# SUSTAINA-Audio-Board.net
KiCad netlist of a schematic drawn in EAGLE
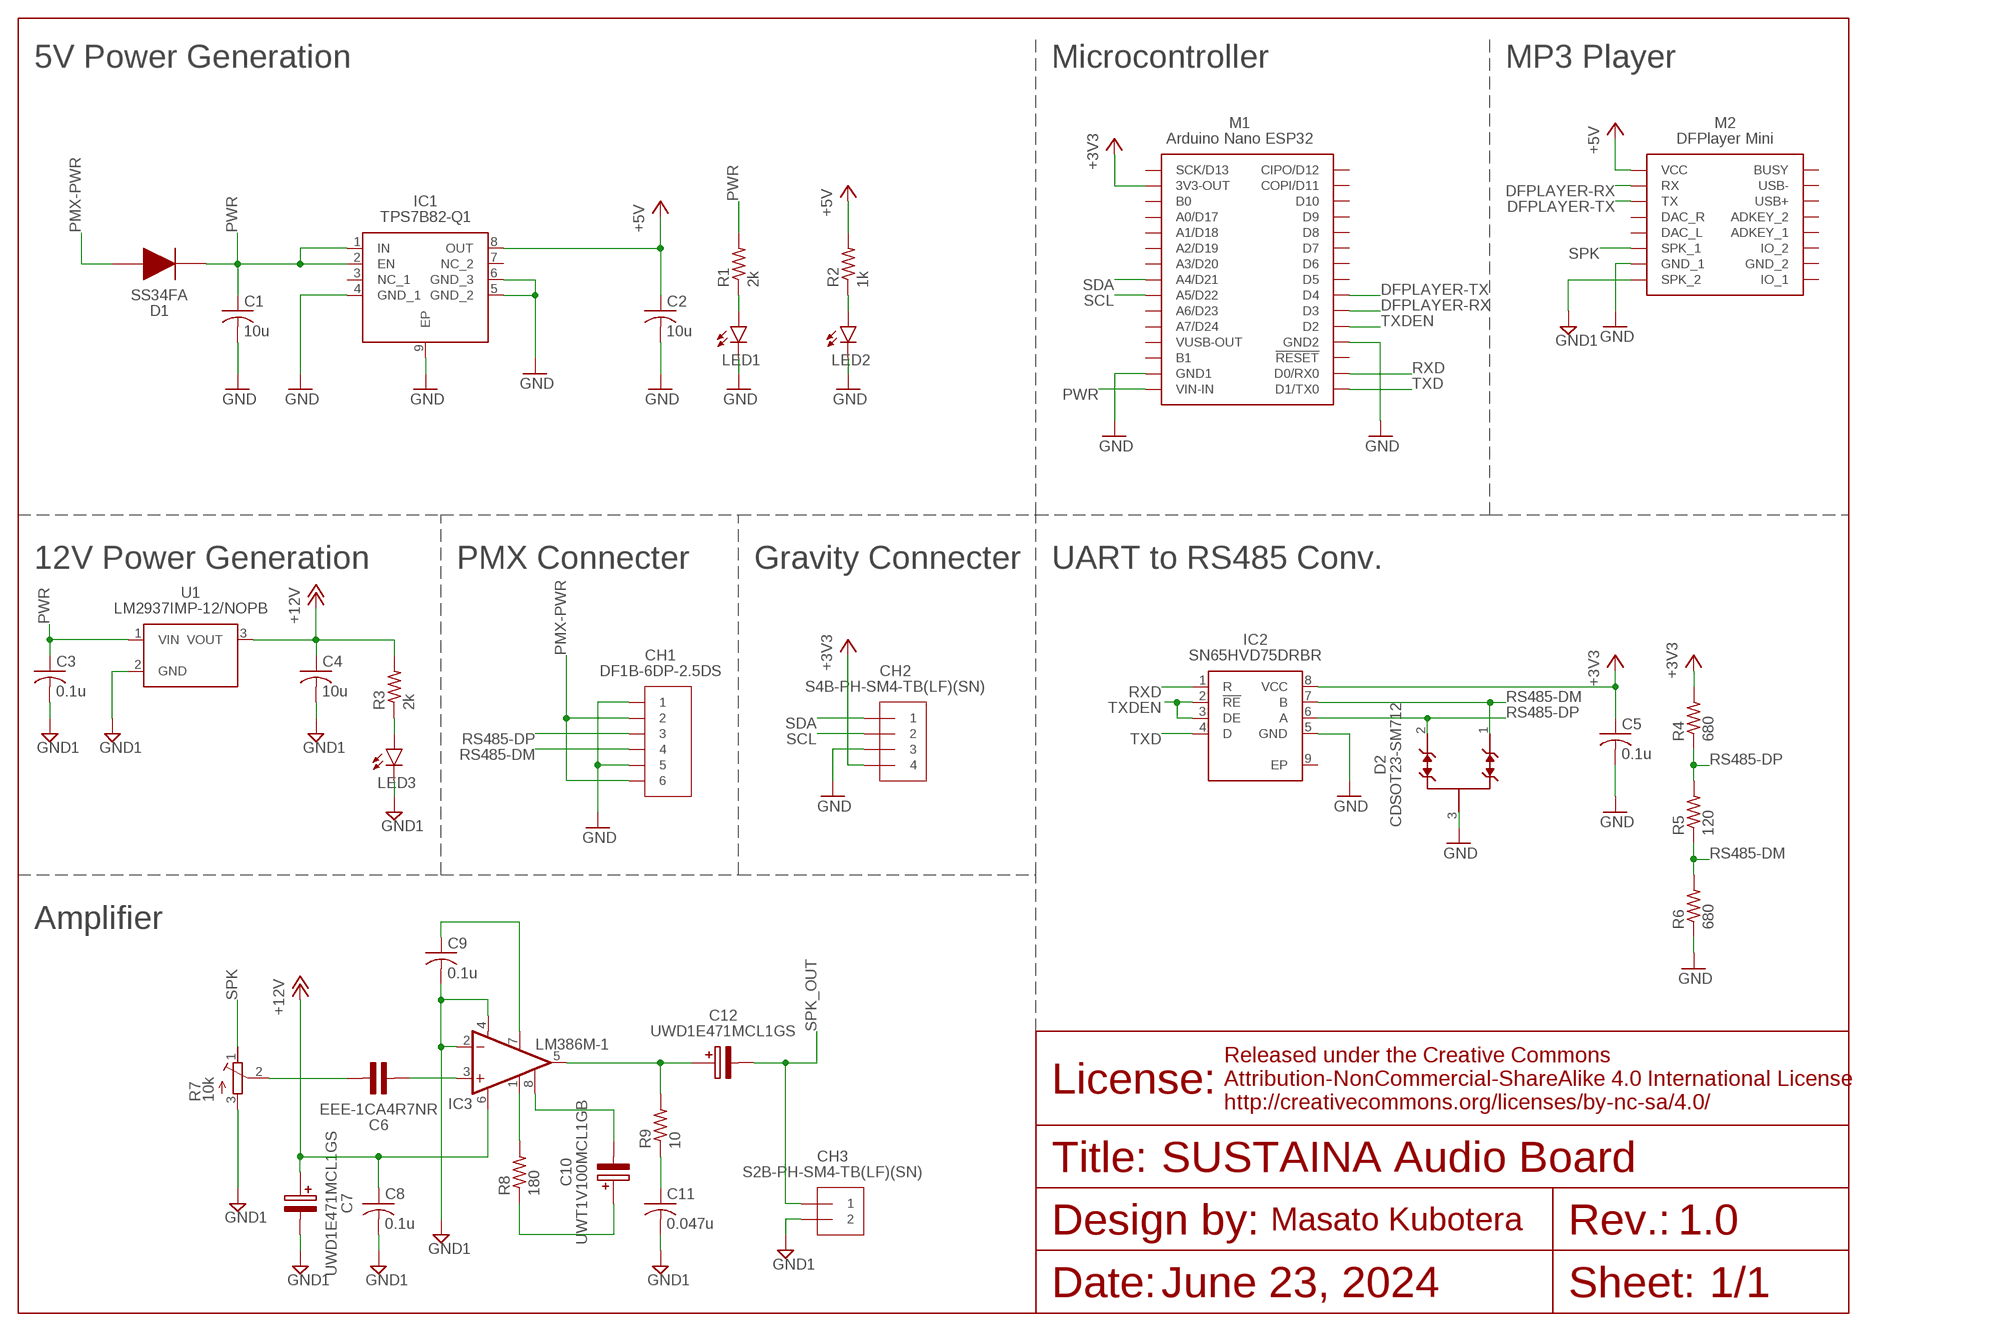
[diagram p0: schematic, sheet 1]

(export (version "E")
  (design (tool "Eeschema 10.0.6"))
  (components
    (comp (ref "C1")
      (value "10u")
      (footprint "eagle-import:C0603")
      (libsource (lib "eagle-import") (part "C-USC0603"))
    )
    (comp (ref "C2")
      (value "10u")
      (footprint "eagle-import:C0603")
      (libsource (lib "eagle-import") (part "C-USC0603"))
    )
    (comp (ref "C3")
      (value "0.1u")
      (footprint "eagle-import:C0603")
      (libsource (lib "eagle-import") (part "C-USC0603"))
    )
    (comp (ref "C4")
      (value "10u")
      (footprint "eagle-import:C0603")
      (libsource (lib "eagle-import") (part "C-USC0603"))
    )
    (comp (ref "C5")
      (value "0.1u")
      (footprint "eagle-import:C0603")
      (libsource (lib "eagle-import") (part "C-USC0603"))
    )
    (comp (ref "C6")
      (value "EEE-1CA4R7NR")
      (footprint "eagle-import:EEE-1CA4R7NR")
      (libsource (lib "eagle-import") (part "EEE-1CA4R7NR"))
    )
    (comp (ref "C7")
      (value "UWD1E471MCL1GS")
      (footprint "eagle-import:UWD1E471MCL1GS")
      (libsource (lib "eagle-import") (part "UWD1E471MCL1GS"))
    )
    (comp (ref "C8")
      (value "0.1u")
      (footprint "eagle-import:C0603")
      (libsource (lib "eagle-import") (part "C-USC0603"))
    )
    (comp (ref "C9")
      (value "0.1u")
      (footprint "eagle-import:C0603")
      (libsource (lib "eagle-import") (part "C-USC0603"))
    )
    (comp (ref "C10")
      (value "UWT1V100MCL1GB")
      (footprint "eagle-import:UWT1V100MCL1GB")
      (libsource (lib "eagle-import") (part "UWT1V100MCL1GB"))
    )
    (comp (ref "C11")
      (value "0.047u")
      (footprint "eagle-import:C050-055X075")
      (libsource (lib "eagle-import") (part "C-US050-055X075"))
    )
    (comp (ref "C12")
      (value "UWD1E471MCL1GS")
      (footprint "eagle-import:UWD1E471MCL1GS")
      (libsource (lib "eagle-import") (part "UWD1E471MCL1GS"))
    )
    (comp (ref "CH1")
      (value "DF1B-6DP-2.5DS")
      (footprint "eagle-import:DF1B-6DP-2.5DS")
      (libsource (lib "eagle-import") (part "DF1B-6DP-2.5DS"))
    )
    (comp (ref "CH2")
      (value "S4B-PH-SM4-TB(LF)(SN)")
      (footprint "eagle-import:S4B-PH-SM4-TB(LF)(SN)")
      (libsource (lib "eagle-import") (part "S4B-PH-SM4-TB(LF)(SN)"))
    )
    (comp (ref "CH3")
      (value "S2B-PH-SM4-TB(LF)(SN)")
      (footprint "eagle-import:S2B-PH-SM4-TB(LF)(SN)")
      (libsource (lib "eagle-import") (part "S2B-PH-SM4-TB(LF)(SN)"))
    )
    (comp (ref "D1")
      (value "SS34FA")
      (footprint "eagle-import:SS34FA")
      (libsource (lib "eagle-import") (part "SS34FA"))
    )
    (comp (ref "D2")
      (value "CDSOT23-SM712")
      (footprint "eagle-import:SOT-23-3")
      (libsource (lib "eagle-import") (part "CDSOT23-SM712"))
    )
    (comp (ref "IC1")
      (value "TPS7B82-Q1")
      (footprint "eagle-import:SOP65P490X110-9N")
      (libsource (lib "eagle-import") (part "TPS7B82-Q1"))
    )
    (comp (ref "IC2")
      (value "SN65HVD75DRBR")
      (footprint "eagle-import:SON65P300X300X100-9N")
      (libsource (lib "eagle-import") (part "SN65HVD75DRBR"))
    )
    (comp (ref "IC3")
      (value "LM386M-1")
      (footprint "eagle-import:SO08")
      (libsource (lib "eagle-import") (part "LM386?-M1"))
    )
    (comp (ref "LED1")
      (value "LEDSML0603")
      (footprint "eagle-import:SML0603")
      (libsource (lib "eagle-import") (part "LEDSML0603"))
    )
    (comp (ref "LED2")
      (value "LEDSML0603")
      (footprint "eagle-import:SML0603")
      (libsource (lib "eagle-import") (part "LEDSML0603"))
    )
    (comp (ref "LED3")
      (value "LEDSML0603")
      (footprint "eagle-import:SML0603")
      (libsource (lib "eagle-import") (part "LEDSML0603"))
    )
    (comp (ref "M1")
      (value "NANO-ESP32")
      (footprint "eagle-import:NANO-ESP32")
      (libsource (lib "eagle-import") (part "NANO-ESP32"))
    )
    (comp (ref "M2")
      (value "DFPLAYER_MINI")
      (footprint "eagle-import:DFPLAYER_MINI")
      (libsource (lib "eagle-import") (part "DFPLAYER_MINI"))
    )
    (comp (ref "R1")
      (value "2k")
      (footprint "eagle-import:R0603")
      (libsource (lib "eagle-import") (part "R-US_R0603"))
    )
    (comp (ref "R2")
      (value "1k")
      (footprint "eagle-import:R0603")
      (libsource (lib "eagle-import") (part "R-US_R0603"))
    )
    (comp (ref "R3")
      (value "2k")
      (footprint "eagle-import:R0603")
      (libsource (lib "eagle-import") (part "R-US_R0603"))
    )
    (comp (ref "R4")
      (value "680")
      (footprint "eagle-import:R0603")
      (libsource (lib "eagle-import") (part "R-US_R0603"))
    )
    (comp (ref "R5")
      (value "120")
      (footprint "eagle-import:R0603")
      (libsource (lib "eagle-import") (part "R-US_R0603"))
    )
    (comp (ref "R6")
      (value "680")
      (footprint "eagle-import:R0603")
      (libsource (lib "eagle-import") (part "R-US_R0603"))
    )
    (comp (ref "R7")
      (value "10k")
      (footprint "eagle-import:RTRIM3006P")
      (libsource (lib "eagle-import") (part "R-TRIMM3006P"))
    )
    (comp (ref "R8")
      (value "180")
      (footprint "eagle-import:R0603")
      (libsource (lib "eagle-import") (part "R-US_R0603"))
    )
    (comp (ref "R9")
      (value "10")
      (footprint "eagle-import:R0603")
      (libsource (lib "eagle-import") (part "R-US_R0603"))
    )
    (comp (ref "U1")
      (value "LM2937IMP-12NOPB")
      (footprint "eagle-import:SOT-223")
      (libsource (lib "eagle-import") (part "LM2937IMP-12NOPB"))
    )
  )
  (nets
    (net (code "1") (name "+3V3") (class "Default")
      (node (ref "C5") (pin "1") (pinfunction "1_1") (pintype "passive"))
      (node (ref "CH2") (pin "4") (pinfunction "4_4") (pintype "bidirectional"))
      (node (ref "IC2") (pin "8") (pinfunction "VCC_8") (pintype "bidirectional"))
      (node (ref "M1") (pin "3V3-OUT") (pinfunction "3V3-OUT_3V3-OUT") (pintype "bidirectional"))
      (node (ref "R4") (pin "2") (pinfunction "2_2") (pintype "passive"))
    )
    (net (code "2") (name "+5V") (class "Default")
      (node (ref "C2") (pin "1") (pinfunction "1_1") (pintype "passive"))
      (node (ref "IC1") (pin "8") (pinfunction "OUT_8") (pintype "bidirectional"))
      (node (ref "M2") (pin "VCC") (pinfunction "VCC_VCC") (pintype "bidirectional"))
      (node (ref "R2") (pin "2") (pinfunction "2_2") (pintype "passive"))
    )
    (net (code "3") (name "+12V") (class "Default")
      (node (ref "C4") (pin "1") (pinfunction "1_1") (pintype "passive"))
      (node (ref "C7") (pin "+") (pinfunction "+_+") (pintype "bidirectional"))
      (node (ref "C8") (pin "1") (pinfunction "1_1") (pintype "passive"))
      (node (ref "IC3") (pin "6") (pinfunction "VS_6") (pintype "power_in"))
      (node (ref "R3") (pin "2") (pinfunction "2_2") (pintype "passive"))
      (node (ref "U1") (pin "3") (pinfunction "VOUT_3") (pintype "bidirectional"))
    )
    (net (code "4") (name "/DFPLAYER-RX") (class "Default")
      (node (ref "M1") (pin "D3") (pinfunction "D3_D3") (pintype "bidirectional"))
      (node (ref "M2") (pin "RX") (pinfunction "RX_RX") (pintype "bidirectional"))
    )
    (net (code "5") (name "/DFPLAYER-TX") (class "Default")
      (node (ref "M1") (pin "D4") (pinfunction "D4_D4") (pintype "bidirectional"))
      (node (ref "M2") (pin "TX") (pinfunction "TX_TX") (pintype "bidirectional"))
    )
    (net (code "6") (name "/PMX-PWR") (class "Default")
      (node (ref "CH1") (pin "2") (pinfunction "2_2") (pintype "bidirectional"))
      (node (ref "CH1") (pin "6") (pinfunction "6_6") (pintype "bidirectional"))
      (node (ref "D1") (pin "2") (pinfunction "2_2") (pintype "bidirectional"))
    )
    (net (code "7") (name "/PWR") (class "Default")
      (node (ref "C1") (pin "1") (pinfunction "1_1") (pintype "passive"))
      (node (ref "C3") (pin "1") (pinfunction "1_1") (pintype "passive"))
      (node (ref "D1") (pin "1") (pinfunction "1_1") (pintype "bidirectional"))
      (node (ref "IC1") (pin "1") (pinfunction "IN_1") (pintype "bidirectional"))
      (node (ref "IC1") (pin "2") (pinfunction "EN_2") (pintype "bidirectional"))
      (node (ref "M1") (pin "VIN-IN") (pinfunction "VIN-IN_VIN-IN") (pintype "bidirectional"))
      (node (ref "R1") (pin "2") (pinfunction "2_2") (pintype "passive"))
      (node (ref "U1") (pin "1") (pinfunction "VIN_1") (pintype "bidirectional"))
    )
    (net (code "8") (name "/RS485-DM") (class "Default")
      (node (ref "CH1") (pin "4") (pinfunction "4_4") (pintype "bidirectional"))
      (node (ref "D2") (pin "1") (pinfunction "1_1") (pintype "bidirectional"))
      (node (ref "IC2") (pin "7") (pinfunction "B_7") (pintype "bidirectional"))
      (node (ref "R5") (pin "1") (pinfunction "1_1") (pintype "passive"))
      (node (ref "R6") (pin "2") (pinfunction "2_2") (pintype "passive"))
    )
    (net (code "9") (name "/RS485-DP") (class "Default")
      (node (ref "CH1") (pin "3") (pinfunction "3_3") (pintype "bidirectional"))
      (node (ref "D2") (pin "2") (pinfunction "2_2") (pintype "bidirectional"))
      (node (ref "IC2") (pin "6") (pinfunction "A_6") (pintype "bidirectional"))
      (node (ref "R4") (pin "1") (pinfunction "1_1") (pintype "passive"))
      (node (ref "R5") (pin "2") (pinfunction "2_2") (pintype "passive"))
    )
    (net (code "10") (name "/RXD") (class "Default")
      (node (ref "IC2") (pin "1") (pinfunction "R_1") (pintype "bidirectional"))
      (node (ref "M1") (pin "D0/RX0") (pinfunction "D0/RX0_D0/RX0") (pintype "bidirectional"))
    )
    (net (code "11") (name "/SCL") (class "Default")
      (node (ref "CH2") (pin "2") (pinfunction "2_2") (pintype "bidirectional"))
      (node (ref "M1") (pin "A5/D22") (pinfunction "A5/D22_A5/D22") (pintype "bidirectional"))
    )
    (net (code "12") (name "/SDA") (class "Default")
      (node (ref "CH2") (pin "1") (pinfunction "1_1") (pintype "bidirectional"))
      (node (ref "M1") (pin "A4/D21") (pinfunction "A4/D21_A4/D21") (pintype "bidirectional"))
    )
    (net (code "13") (name "/SPK") (class "Default")
      (node (ref "M2") (pin "SPK1") (pinfunction "SPK_1_SPK1") (pintype "bidirectional"))
      (node (ref "R7") (pin "1") (pinfunction "E_1") (pintype "passive"))
    )
    (net (code "14") (name "/SPK_OUT") (class "Default")
      (node (ref "C12") (pin "-") (pinfunction "-_-") (pintype "bidirectional"))
      (node (ref "CH3") (pin "1") (pinfunction "1_1") (pintype "bidirectional"))
    )
    (net (code "15") (name "/TXD") (class "Default")
      (node (ref "IC2") (pin "4") (pinfunction "D_4") (pintype "bidirectional"))
      (node (ref "M1") (pin "D1/TX0") (pinfunction "D1/TX0_D1/TX0") (pintype "bidirectional"))
    )
    (net (code "16") (name "/TXDEN") (class "Default")
      (node (ref "IC2") (pin "2") (pinfunction "~{RE}_2") (pintype "bidirectional"))
      (node (ref "IC2") (pin "3") (pinfunction "DE_3") (pintype "bidirectional"))
      (node (ref "M1") (pin "D2") (pinfunction "D2_D2") (pintype "bidirectional"))
    )
    (net (code "17") (name "GND") (class "Default")
      (node (ref "C1") (pin "2") (pinfunction "2_2") (pintype "passive"))
      (node (ref "C2") (pin "2") (pinfunction "2_2") (pintype "passive"))
      (node (ref "C5") (pin "2") (pinfunction "2_2") (pintype "passive"))
      (node (ref "CH1") (pin "1") (pinfunction "1_1") (pintype "bidirectional"))
      (node (ref "CH1") (pin "5") (pinfunction "5_5") (pintype "bidirectional"))
      (node (ref "CH2") (pin "3") (pinfunction "3_3") (pintype "bidirectional"))
      (node (ref "D2") (pin "3") (pinfunction "3_3") (pintype "bidirectional"))
      (node (ref "IC1") (pin "4") (pinfunction "GND_1_4") (pintype "bidirectional"))
      (node (ref "IC1") (pin "5") (pinfunction "GND_2_5") (pintype "bidirectional"))
      (node (ref "IC1") (pin "6") (pinfunction "GND_3_6") (pintype "bidirectional"))
      (node (ref "IC1") (pin "9") (pinfunction "EP_9") (pintype "bidirectional"))
      (node (ref "IC2") (pin "5") (pinfunction "GND_5") (pintype "bidirectional"))
      (node (ref "LED1") (pin "C") (pinfunction "C_C") (pintype "passive"))
      (node (ref "LED2") (pin "C") (pinfunction "C_C") (pintype "passive"))
      (node (ref "M1") (pin "GND1") (pinfunction "GND1_GND1") (pintype "bidirectional"))
      (node (ref "M1") (pin "GND2") (pinfunction "GND2_GND2") (pintype "bidirectional"))
      (node (ref "M2") (pin "GND_1") (pinfunction "GND_1_GND_1") (pintype "bidirectional"))
      (node (ref "R6") (pin "1") (pinfunction "1_1") (pintype "passive"))
    )
    (net (code "18") (name "GND1") (class "Default")
      (node (ref "C11") (pin "2") (pinfunction "2_2") (pintype "passive"))
      (node (ref "C3") (pin "2") (pinfunction "2_2") (pintype "passive"))
      (node (ref "C4") (pin "2") (pinfunction "2_2") (pintype "passive"))
      (node (ref "C7") (pin "-") (pinfunction "-_-") (pintype "bidirectional"))
      (node (ref "C8") (pin "2") (pinfunction "2_2") (pintype "passive"))
      (node (ref "C9") (pin "2") (pinfunction "2_2") (pintype "passive"))
      (node (ref "CH3") (pin "2") (pinfunction "2_2") (pintype "bidirectional"))
      (node (ref "IC3") (pin "2") (pinfunction "-IN_2") (pintype "input"))
      (node (ref "IC3") (pin "4") (pinfunction "GND_4") (pintype "power_in"))
      (node (ref "LED3") (pin "C") (pinfunction "C_C") (pintype "passive"))
      (node (ref "M2") (pin "SPK2") (pinfunction "SPK_2_SPK2") (pintype "bidirectional"))
      (node (ref "R7") (pin "3") (pinfunction "A_3") (pintype "passive"))
      (node (ref "U1") (pin "2") (pinfunction "GND_2") (pintype "bidirectional"))
    )
    (net (code "19") (name "Net-(C10-Pad+)") (class "Default")
      (node (ref "C10") (pin "+") (pinfunction "+_+") (pintype "bidirectional"))
      (node (ref "R8") (pin "1") (pinfunction "1_1") (pintype "passive"))
    )
    (net (code "20") (name "Net-(C10-Pad-)") (class "Default")
      (node (ref "C10") (pin "-") (pinfunction "-_-") (pintype "bidirectional"))
      (node (ref "IC3") (pin "8") (pinfunction "GAIN_8") (pintype "passive"))
    )
    (net (code "21") (name "Net-(C11-Pad1)") (class "Default")
      (node (ref "C11") (pin "1") (pinfunction "1_1") (pintype "passive"))
      (node (ref "R9") (pin "1") (pinfunction "1_1") (pintype "passive"))
    )
    (net (code "22") (name "Net-(IC3-+IN)") (class "Default")
      (node (ref "C6") (pin "1") (pinfunction "1_1") (pintype "bidirectional"))
      (node (ref "IC3") (pin "3") (pinfunction "+IN_3") (pintype "input"))
    )
    (net (code "23") (name "Net-(IC3-BYPASS)") (class "Default")
      (node (ref "C9") (pin "1") (pinfunction "1_1") (pintype "passive"))
      (node (ref "IC3") (pin "7") (pinfunction "BYPASS_7") (pintype "passive"))
    )
    (net (code "24") (name "Net-(IC3-GAIN-Pad1)") (class "Default")
      (node (ref "IC3") (pin "1") (pinfunction "GAIN_1") (pintype "passive"))
      (node (ref "R8") (pin "2") (pinfunction "2_2") (pintype "passive"))
    )
    (net (code "25") (name "Net-(IC3-OUT)") (class "Default")
      (node (ref "C12") (pin "+") (pinfunction "+_+") (pintype "bidirectional"))
      (node (ref "IC3") (pin "5") (pinfunction "OUT_5") (pintype "output"))
      (node (ref "R9") (pin "2") (pinfunction "2_2") (pintype "passive"))
    )
    (net (code "26") (name "Net-(LED1-PadA)") (class "Default")
      (node (ref "LED1") (pin "A") (pinfunction "A_A") (pintype "passive"))
      (node (ref "R1") (pin "1") (pinfunction "1_1") (pintype "passive"))
    )
    (net (code "27") (name "Net-(LED2-PadA)") (class "Default")
      (node (ref "LED2") (pin "A") (pinfunction "A_A") (pintype "passive"))
      (node (ref "R2") (pin "1") (pinfunction "1_1") (pintype "passive"))
    )
    (net (code "28") (name "Net-(LED3-PadA)") (class "Default")
      (node (ref "LED3") (pin "A") (pinfunction "A_A") (pintype "passive"))
      (node (ref "R3") (pin "1") (pinfunction "1_1") (pintype "passive"))
    )
    (net (code "29") (name "Net-(R7-S)") (class "Default")
      (node (ref "C6") (pin "2") (pinfunction "2_2") (pintype "bidirectional"))
      (node (ref "R7") (pin "2") (pinfunction "S_2") (pintype "passive"))
    )
    (net (code "30") (name "unconnected-(IC1-NC_1-Pad3)") (class "Default")
      (node (ref "IC1") (pin "3") (pinfunction "NC_1_3") (pintype "no_connect"))
    )
    (net (code "31") (name "unconnected-(IC1-NC_2-Pad7)") (class "Default")
      (node (ref "IC1") (pin "7") (pinfunction "NC_2_7") (pintype "no_connect"))
    )
    (net (code "32") (name "unconnected-(IC2-EP-Pad9)") (class "Default")
      (node (ref "IC2") (pin "9") (pinfunction "EP_9") (pintype "bidirectional"))
    )
    (net (code "33") (name "unconnected-(M1-PadA0{slash}D17)") (class "Default")
      (node (ref "M1") (pin "A0/D17") (pinfunction "A0/D17_A0/D17") (pintype "bidirectional"))
    )
    (net (code "34") (name "unconnected-(M1-PadA1{slash}D18)") (class "Default")
      (node (ref "M1") (pin "A1/D18") (pinfunction "A1/D18_A1/D18") (pintype "bidirectional"))
    )
    (net (code "35") (name "unconnected-(M1-PadA2{slash}D19)") (class "Default")
      (node (ref "M1") (pin "A2/D19") (pinfunction "A2/D19_A2/D19") (pintype "bidirectional"))
    )
    (net (code "36") (name "unconnected-(M1-PadA3{slash}D20)") (class "Default")
      (node (ref "M1") (pin "A3/D20") (pinfunction "A3/D20_A3/D20") (pintype "bidirectional"))
    )
    (net (code "37") (name "unconnected-(M1-PadA6{slash}D23)") (class "Default")
      (node (ref "M1") (pin "A6/D23") (pinfunction "A6/D23_A6/D23") (pintype "bidirectional"))
    )
    (net (code "38") (name "unconnected-(M1-PadA7{slash}D24)") (class "Default")
      (node (ref "M1") (pin "A7/D24") (pinfunction "A7/D24_A7/D24") (pintype "bidirectional"))
    )
    (net (code "39") (name "unconnected-(M1-PadB0)") (class "Default")
      (node (ref "M1") (pin "B0") (pinfunction "B0_B0") (pintype "bidirectional"))
    )
    (net (code "40") (name "unconnected-(M1-PadB1)") (class "Default")
      (node (ref "M1") (pin "B1") (pinfunction "B1_B1") (pintype "bidirectional"))
    )
    (net (code "41") (name "unconnected-(M1-PadCIPO{slash}D12)") (class "Default")
      (node (ref "M1") (pin "CIPO/D12") (pinfunction "CIPO/D12_CIPO/D12") (pintype "bidirectional"))
    )
    (net (code "42") (name "unconnected-(M1-PadCOPI{slash}D11)") (class "Default")
      (node (ref "M1") (pin "COPI/D11") (pinfunction "COPI/D11_COPI/D11") (pintype "bidirectional"))
    )
    (net (code "43") (name "unconnected-(M1-PadD5)") (class "Default")
      (node (ref "M1") (pin "D5") (pinfunction "D5_D5") (pintype "bidirectional"))
    )
    (net (code "44") (name "unconnected-(M1-PadD6)") (class "Default")
      (node (ref "M1") (pin "D6") (pinfunction "D6_D6") (pintype "bidirectional"))
    )
    (net (code "45") (name "unconnected-(M1-PadD7)") (class "Default")
      (node (ref "M1") (pin "D7") (pinfunction "D7_D7") (pintype "bidirectional"))
    )
    (net (code "46") (name "unconnected-(M1-PadD8)") (class "Default")
      (node (ref "M1") (pin "D8") (pinfunction "D8_D8") (pintype "bidirectional"))
    )
    (net (code "47") (name "unconnected-(M1-PadD9)") (class "Default")
      (node (ref "M1") (pin "D9") (pinfunction "D9_D9") (pintype "bidirectional"))
    )
    (net (code "48") (name "unconnected-(M1-PadD10)") (class "Default")
      (node (ref "M1") (pin "D10") (pinfunction "D10_D10") (pintype "bidirectional"))
    )
    (net (code "49") (name "unconnected-(M1-PadSCK{slash}D13)") (class "Default")
      (node (ref "M1") (pin "SCK/D13") (pinfunction "SCK/D13_SCK/D13") (pintype "bidirectional"))
    )
    (net (code "50") (name "unconnected-(M1-PadVUSB-OUT)") (class "Default")
      (node (ref "M1") (pin "VUSB-OUT") (pinfunction "VUSB-OUT_VUSB-OUT") (pintype "bidirectional"))
    )
    (net (code "51") (name "unconnected-(M1-~{RESET}-Pad!RESET)") (class "Default")
      (node (ref "M1") (pin "!RESET") (pinfunction "~{RESET}_!RESET") (pintype "bidirectional"))
    )
    (net (code "52") (name "unconnected-(M2-ADKEY_1-PadADKEY1)") (class "Default")
      (node (ref "M2") (pin "ADKEY1") (pinfunction "ADKEY_1_ADKEY1") (pintype "bidirectional"))
    )
    (net (code "53") (name "unconnected-(M2-ADKEY_2-PadADKEY2)") (class "Default")
      (node (ref "M2") (pin "ADKEY2") (pinfunction "ADKEY_2_ADKEY2") (pintype "bidirectional"))
    )
    (net (code "54") (name "unconnected-(M2-IO_1-PadIO1)") (class "Default")
      (node (ref "M2") (pin "IO1") (pinfunction "IO_1_IO1") (pintype "bidirectional"))
    )
    (net (code "55") (name "unconnected-(M2-IO_2-PadIO2)") (class "Default")
      (node (ref "M2") (pin "IO2") (pinfunction "IO_2_IO2") (pintype "bidirectional"))
    )
    (net (code "56") (name "unconnected-(M2-PadBUSY)") (class "Default")
      (node (ref "M2") (pin "BUSY") (pinfunction "BUSY_BUSY") (pintype "bidirectional"))
    )
    (net (code "57") (name "unconnected-(M2-PadDAC_L)") (class "Default")
      (node (ref "M2") (pin "DAC_L") (pinfunction "DAC_L_DAC_L") (pintype "bidirectional"))
    )
    (net (code "58") (name "unconnected-(M2-PadDAC_R)") (class "Default")
      (node (ref "M2") (pin "DAC_R") (pinfunction "DAC_R_DAC_R") (pintype "bidirectional"))
    )
    (net (code "59") (name "unconnected-(M2-PadGND_2)") (class "Default")
      (node (ref "M2") (pin "GND_2") (pinfunction "GND_2_GND_2") (pintype "bidirectional"))
    )
    (net (code "60") (name "unconnected-(M2-PadUSB+)") (class "Default")
      (node (ref "M2") (pin "USB+") (pinfunction "USB+_USB+") (pintype "bidirectional"))
    )
    (net (code "61") (name "unconnected-(M2-PadUSB-)") (class "Default")
      (node (ref "M2") (pin "USB-") (pinfunction "USB-_USB-") (pintype "bidirectional"))
    )
  )
)
